# Interface.net
KiCad netlist of a schematic drawn in EAGLE
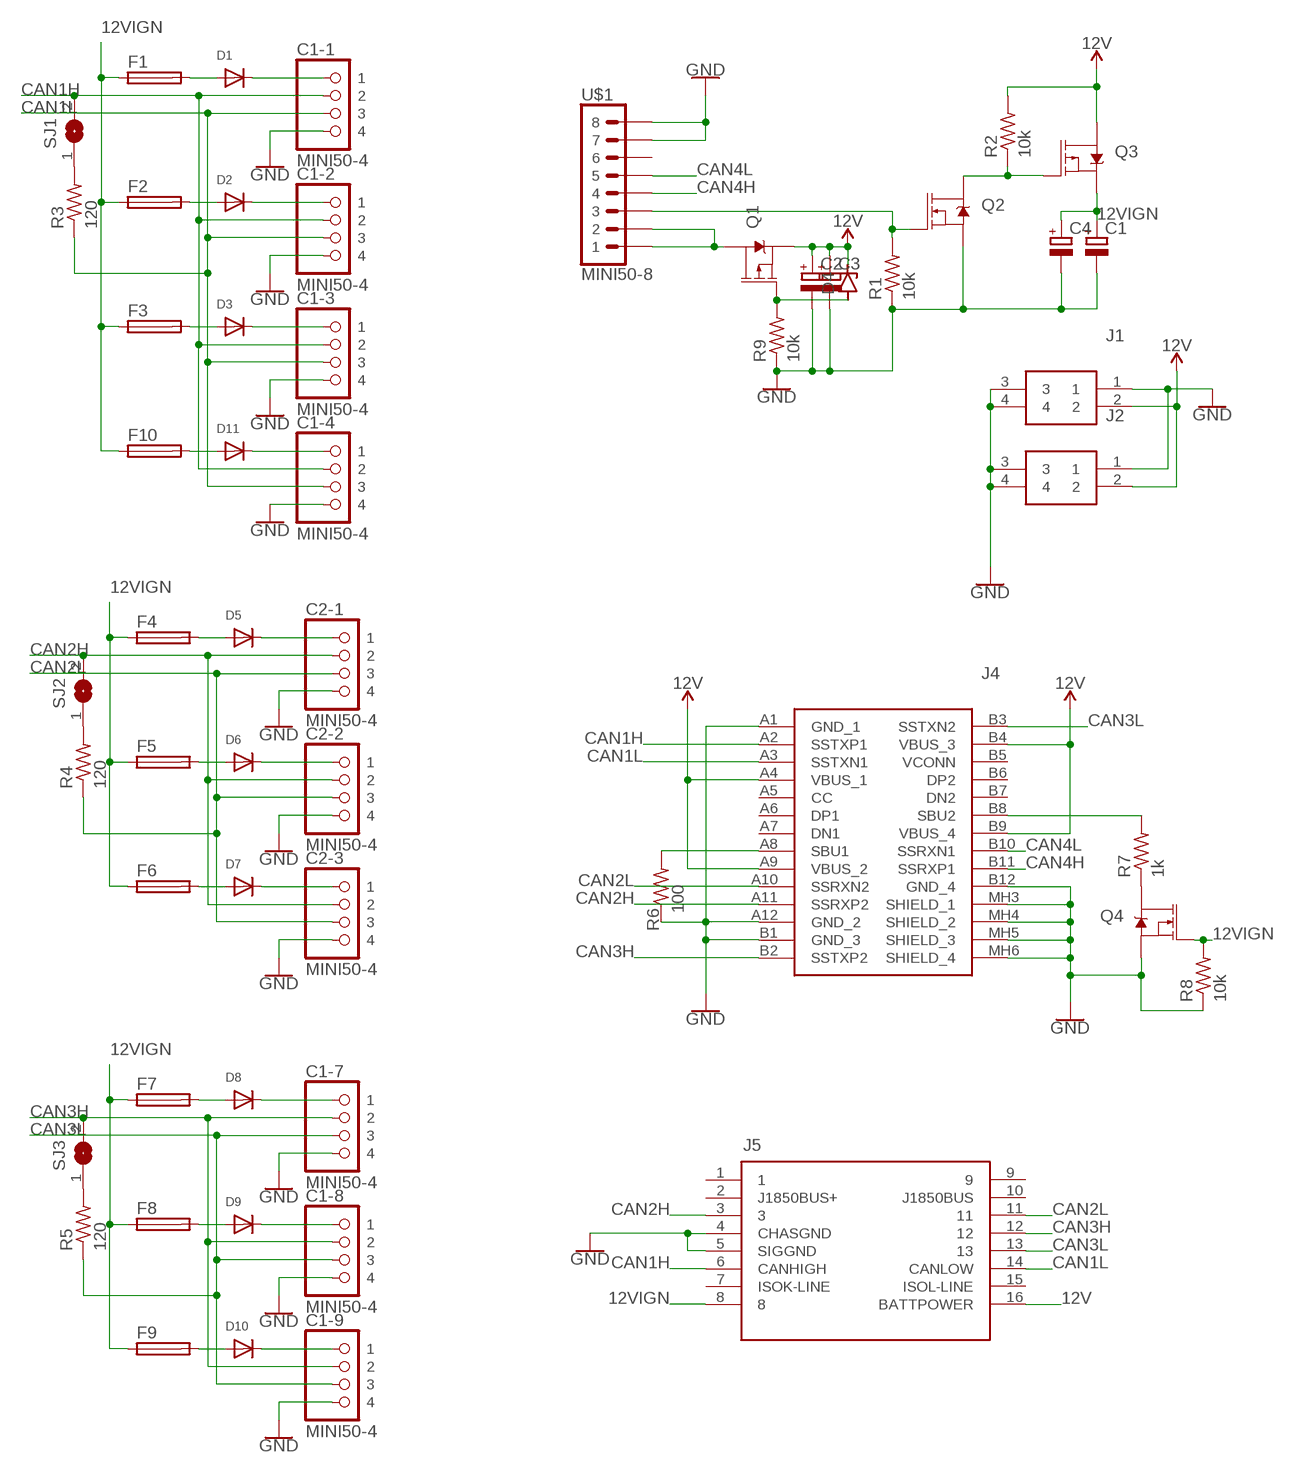
[diagram p0: schematic, sheet 1]

(export (version "E")
  (design (tool "Eeschema 10.0.6"))
  (components
    (comp (ref "C1")
      (value "CPOL-EU153CLV-1010")
      (footprint "eagle-import:153CLV-1010")
      (libsource (lib "eagle-import") (part "CPOL-EU153CLV-1010"))
    )
    (comp (ref "C1-1")
      (value "MINI50-4")
      (footprint "eagle-import:MINI50")
      (libsource (lib "eagle-import") (part "MINI50-4"))
    )
    (comp (ref "C1-2")
      (value "MINI50-4")
      (footprint "eagle-import:MINI50")
      (libsource (lib "eagle-import") (part "MINI50-4"))
    )
    (comp (ref "C1-3")
      (value "MINI50-4")
      (footprint "eagle-import:MINI50")
      (libsource (lib "eagle-import") (part "MINI50-4"))
    )
    (comp (ref "C1-4")
      (value "MINI50-4")
      (footprint "eagle-import:MINI50")
      (libsource (lib "eagle-import") (part "MINI50-4"))
    )
    (comp (ref "C1-7")
      (value "MINI50-4")
      (footprint "eagle-import:MINI50")
      (libsource (lib "eagle-import") (part "MINI50-4"))
    )
    (comp (ref "C1-8")
      (value "MINI50-4")
      (footprint "eagle-import:MINI50")
      (libsource (lib "eagle-import") (part "MINI50-4"))
    )
    (comp (ref "C1-9")
      (value "MINI50-4")
      (footprint "eagle-import:MINI50")
      (libsource (lib "eagle-import") (part "MINI50-4"))
    )
    (comp (ref "C2")
      (value "CPOL-EU153CLV-1010")
      (footprint "eagle-import:153CLV-1010")
      (libsource (lib "eagle-import") (part "CPOL-EU153CLV-1010"))
    )
    (comp (ref "C2-1")
      (value "MINI50-4")
      (footprint "eagle-import:MINI50")
      (libsource (lib "eagle-import") (part "MINI50-4"))
    )
    (comp (ref "C2-2")
      (value "MINI50-4")
      (footprint "eagle-import:MINI50")
      (libsource (lib "eagle-import") (part "MINI50-4"))
    )
    (comp (ref "C2-3")
      (value "MINI50-4")
      (footprint "eagle-import:MINI50")
      (libsource (lib "eagle-import") (part "MINI50-4"))
    )
    (comp (ref "C3")
      (value "CPOL-EU153CLV-0505")
      (footprint "eagle-import:153CLV-0505")
      (libsource (lib "eagle-import") (part "CPOL-EU153CLV-0505"))
    )
    (comp (ref "C4")
      (value "CPOL-EU153CLV-0505")
      (footprint "eagle-import:153CLV-0505")
      (libsource (lib "eagle-import") (part "CPOL-EU153CLV-0505"))
    )
    (comp (ref "D1")
      (value "DIODESOD-323F")
      (footprint "eagle-import:SOD-323F")
      (libsource (lib "eagle-import") (part "DIODESOD-323F"))
    )
    (comp (ref "D2")
      (value "DIODESOD-323F")
      (footprint "eagle-import:SOD-323F")
      (libsource (lib "eagle-import") (part "DIODESOD-323F"))
    )
    (comp (ref "D3")
      (value "DIODESOD-323F")
      (footprint "eagle-import:SOD-323F")
      (libsource (lib "eagle-import") (part "DIODESOD-323F"))
    )
    (comp (ref "D4")
      (value "ZENER_DO-219-AB(SOD123F)")
      (footprint "eagle-import:SODFL3718X115")
      (libsource (lib "eagle-import") (part "ZENERDO-219-AB(SOD123F)_"))
    )
    (comp (ref "D5")
      (value "DIODESOD-323F")
      (footprint "eagle-import:SOD-323F")
      (libsource (lib "eagle-import") (part "DIODESOD-323F"))
    )
    (comp (ref "D6")
      (value "DIODESOD-323F")
      (footprint "eagle-import:SOD-323F")
      (libsource (lib "eagle-import") (part "DIODESOD-323F"))
    )
    (comp (ref "D7")
      (value "DIODESOD-323F")
      (footprint "eagle-import:SOD-323F")
      (libsource (lib "eagle-import") (part "DIODESOD-323F"))
    )
    (comp (ref "D8")
      (value "DIODESOD-323F")
      (footprint "eagle-import:SOD-323F")
      (libsource (lib "eagle-import") (part "DIODESOD-323F"))
    )
    (comp (ref "D9")
      (value "DIODESOD-323F")
      (footprint "eagle-import:SOD-323F")
      (libsource (lib "eagle-import") (part "DIODESOD-323F"))
    )
    (comp (ref "D10")
      (value "DIODESOD-323F")
      (footprint "eagle-import:SOD-323F")
      (libsource (lib "eagle-import") (part "DIODESOD-323F"))
    )
    (comp (ref "D11")
      (value "DIODESOD-323F")
      (footprint "eagle-import:SOD-323F")
      (libsource (lib "eagle-import") (part "DIODESOD-323F"))
    )
    (comp (ref "F1")
      (value "FUSE_CHIP-1206(3216-METRIC)")
      (footprint "eagle-import:FUSC3215X82N")
      (libsource (lib "eagle-import") (part "FUSECHIP-1206(3216-METRIC)_"))
    )
    (comp (ref "F2")
      (value "FUSE_CHIP-1206(3216-METRIC)")
      (footprint "eagle-import:FUSC3215X82N")
      (libsource (lib "eagle-import") (part "FUSECHIP-1206(3216-METRIC)_"))
    )
    (comp (ref "F3")
      (value "FUSE_CHIP-1206(3216-METRIC)")
      (footprint "eagle-import:FUSC3215X82N")
      (libsource (lib "eagle-import") (part "FUSECHIP-1206(3216-METRIC)_"))
    )
    (comp (ref "F4")
      (value "FUSE_CHIP-1206(3216-METRIC)")
      (footprint "eagle-import:FUSC3215X82N")
      (libsource (lib "eagle-import") (part "FUSECHIP-1206(3216-METRIC)_"))
    )
    (comp (ref "F5")
      (value "FUSE_CHIP-1206(3216-METRIC)")
      (footprint "eagle-import:FUSC3215X82N")
      (libsource (lib "eagle-import") (part "FUSECHIP-1206(3216-METRIC)_"))
    )
    (comp (ref "F6")
      (value "FUSE_CHIP-1206(3216-METRIC)")
      (footprint "eagle-import:FUSC3215X82N")
      (libsource (lib "eagle-import") (part "FUSECHIP-1206(3216-METRIC)_"))
    )
    (comp (ref "F7")
      (value "FUSE_CHIP-1206(3216-METRIC)")
      (footprint "eagle-import:FUSC3215X82N")
      (libsource (lib "eagle-import") (part "FUSECHIP-1206(3216-METRIC)_"))
    )
    (comp (ref "F8")
      (value "FUSE_CHIP-1206(3216-METRIC)")
      (footprint "eagle-import:FUSC3215X82N")
      (libsource (lib "eagle-import") (part "FUSECHIP-1206(3216-METRIC)_"))
    )
    (comp (ref "F9")
      (value "FUSE_CHIP-1206(3216-METRIC)")
      (footprint "eagle-import:FUSC3215X82N")
      (libsource (lib "eagle-import") (part "FUSECHIP-1206(3216-METRIC)_"))
    )
    (comp (ref "F10")
      (value "FUSE_CHIP-1206(3216-METRIC)")
      (footprint "eagle-import:FUSC3215X82N")
      (libsource (lib "eagle-import") (part "FUSECHIP-1206(3216-METRIC)_"))
    )
    (comp (ref "J1")
      (value "34912-8020")
      (footprint "eagle-import:0349128020")
      (fields (field (name "MOUSER_PART_NUMBER") "538-34912-8020"))
      (libsource (lib "eagle-import") (part "34912-8020"))
    )
    (comp (ref "J2")
      (value "34912-8020")
      (footprint "eagle-import:0349128020")
      (fields (field (name "MOUSER_PART_NUMBER") "538-34912-8020"))
      (libsource (lib "eagle-import") (part "34912-8020"))
    )
    (comp (ref "J4")
      (value "632722110112")
      (footprint "eagle-import:632722110112")
      (fields (field (name "MOUSER_PART_NUMBER") "710-632722110112"))
      (libsource (lib "eagle-import") (part "632722110112"))
    )
    (comp (ref "J5")
      (value "OBDII-FEMALEFEMALE")
      (footprint "eagle-import:OBDII-FEMALE")
      (libsource (lib "eagle-import") (part "OBDII-FEMALEFEMALE"))
    )
    (comp (ref "Q1")
      (value "6.5A/20V/35mΩ")
      (footprint "eagle-import:SO08")
      (libsource (lib "eagle-import") (part "MOSFET_PCH-KI4435DY"))
    )
    (comp (ref "Q2")
      (value "5.8A/30V/35mΩ")
      (footprint "eagle-import:SOT23-3")
      (libsource (lib "eagle-import") (part "MOSFET-NCH-AO3404A"))
    )
    (comp (ref "Q3")
      (value "6.5A/20V/35mΩ")
      (footprint "eagle-import:SO08")
      (libsource (lib "eagle-import") (part "MOSFET_PCH-KI4435DY"))
    )
    (comp (ref "Q4")
      (value "5.8A/30V/35mΩ")
      (footprint "eagle-import:SOT23-3")
      (libsource (lib "eagle-import") (part "MOSFET-NCH-AO3404A"))
    )
    (comp (ref "R1")
      (value "10k")
      (footprint "eagle-import:0402-R")
      (libsource (lib "eagle-import") (part "R0402"))
    )
    (comp (ref "R2")
      (value "10k")
      (footprint "eagle-import:0402-R")
      (libsource (lib "eagle-import") (part "R0402"))
    )
    (comp (ref "R3")
      (value "120")
      (footprint "eagle-import:0402-R")
      (libsource (lib "eagle-import") (part "R0402"))
    )
    (comp (ref "R4")
      (value "120")
      (footprint "eagle-import:0402-R")
      (libsource (lib "eagle-import") (part "R0402"))
    )
    (comp (ref "R5")
      (value "120")
      (footprint "eagle-import:0402-R")
      (libsource (lib "eagle-import") (part "R0402"))
    )
    (comp (ref "R6")
      (value "100")
      (footprint "eagle-import:0402-R")
      (libsource (lib "eagle-import") (part "R0402"))
    )
    (comp (ref "R7")
      (value "1k")
      (footprint "eagle-import:0402-R")
      (libsource (lib "eagle-import") (part "R0402"))
    )
    (comp (ref "R8")
      (value "10k")
      (footprint "eagle-import:0402-R")
      (libsource (lib "eagle-import") (part "R0402"))
    )
    (comp (ref "R9")
      (value "10k")
      (footprint "eagle-import:0402-R")
      (libsource (lib "eagle-import") (part "R0402"))
    )
    (comp (ref "SJ1") (value "SJ") (footprint "eagle-import:SJ") (libsource (lib "eagle-import") (part "SJ")))
    (comp (ref "SJ2") (value "SJ") (footprint "eagle-import:SJ") (libsource (lib "eagle-import") (part "SJ")))
    (comp (ref "SJ3") (value "SJ") (footprint "eagle-import:SJ") (libsource (lib "eagle-import") (part "SJ")))
    (comp (ref "U$1")
      (value "MINI50-8")
      (footprint "eagle-import:MINI50-8")
      (libsource (lib "eagle-import") (part "MINI50-8"))
    )
  )
  (nets
    (net (code "1") (name "/12VIGN") (class "Default")
      (node (ref "C1") (pin "+") (pinfunction "+_+") (pintype "passive"))
      (node (ref "C4") (pin "+") (pinfunction "+_+") (pintype "passive"))
      (node (ref "F1") (pin "1") (pinfunction "1_1") (pintype "passive"))
      (node (ref "F10") (pin "1") (pinfunction "1_1") (pintype "passive"))
      (node (ref "F2") (pin "1") (pinfunction "1_1") (pintype "passive"))
      (node (ref "F3") (pin "1") (pinfunction "1_1") (pintype "passive"))
      (node (ref "F4") (pin "1") (pinfunction "1_1") (pintype "passive"))
      (node (ref "F5") (pin "1") (pinfunction "1_1") (pintype "passive"))
      (node (ref "F6") (pin "1") (pinfunction "1_1") (pintype "passive"))
      (node (ref "F7") (pin "1") (pinfunction "1_1") (pintype "passive"))
      (node (ref "F8") (pin "1") (pinfunction "1_1") (pintype "passive"))
      (node (ref "F9") (pin "1") (pinfunction "1_1") (pintype "passive"))
      (node (ref "J5") (pin "8") (pinfunction "8_8") (pintype "bidirectional"))
      (node (ref "Q3") (pin "1") (pinfunction "S_1") (pintype "bidirectional"))
      (node (ref "Q3") (pin "2") (pinfunction "S_2") (pintype "bidirectional"))
      (node (ref "Q3") (pin "3") (pinfunction "S_3") (pintype "bidirectional"))
      (node (ref "Q4") (pin "1") (pinfunction "G_1") (pintype "bidirectional"))
      (node (ref "R8") (pin "2") (pinfunction "2_2") (pintype "passive"))
    )
    (net (code "2") (name "/CAN1H") (class "Default")
      (node (ref "C1-1") (pin "3") (pinfunction "2_3") (pintype "passive"))
      (node (ref "C1-2") (pin "3") (pinfunction "2_3") (pintype "passive"))
      (node (ref "C1-3") (pin "3") (pinfunction "2_3") (pintype "passive"))
      (node (ref "C1-4") (pin "3") (pinfunction "2_3") (pintype "passive"))
      (node (ref "J4") (pin "A2") (pinfunction "SSTXP1_A2") (pintype "bidirectional"))
      (node (ref "J5") (pin "6") (pinfunction "CANHIGH_6") (pintype "bidirectional"))
      (node (ref "SJ1") (pin "2") (pinfunction "2_2") (pintype "passive"))
    )
    (net (code "3") (name "/CAN1L") (class "Default")
      (node (ref "C1-1") (pin "2") (pinfunction "3_2") (pintype "passive"))
      (node (ref "C1-2") (pin "2") (pinfunction "3_2") (pintype "passive"))
      (node (ref "C1-3") (pin "2") (pinfunction "3_2") (pintype "passive"))
      (node (ref "C1-4") (pin "2") (pinfunction "3_2") (pintype "passive"))
      (node (ref "J4") (pin "A3") (pinfunction "SSTXN1_A3") (pintype "bidirectional"))
      (node (ref "J5") (pin "14") (pinfunction "CANLOW_14") (pintype "bidirectional"))
      (node (ref "R3") (pin "1") (pinfunction "1_1") (pintype "passive"))
    )
    (net (code "4") (name "/CAN2H") (class "Default")
      (node (ref "C2-1") (pin "3") (pinfunction "2_3") (pintype "passive"))
      (node (ref "C2-2") (pin "3") (pinfunction "2_3") (pintype "passive"))
      (node (ref "C2-3") (pin "3") (pinfunction "2_3") (pintype "passive"))
      (node (ref "J4") (pin "A11") (pinfunction "SSRXP2_A11") (pintype "bidirectional"))
      (node (ref "J5") (pin "3") (pinfunction "3_3") (pintype "bidirectional"))
      (node (ref "SJ2") (pin "2") (pinfunction "2_2") (pintype "passive"))
    )
    (net (code "5") (name "/CAN2L") (class "Default")
      (node (ref "C2-1") (pin "2") (pinfunction "3_2") (pintype "passive"))
      (node (ref "C2-2") (pin "2") (pinfunction "3_2") (pintype "passive"))
      (node (ref "C2-3") (pin "2") (pinfunction "3_2") (pintype "passive"))
      (node (ref "J4") (pin "A10") (pinfunction "SSRXN2_A10") (pintype "bidirectional"))
      (node (ref "J5") (pin "11") (pinfunction "11_11") (pintype "bidirectional"))
      (node (ref "R4") (pin "1") (pinfunction "1_1") (pintype "passive"))
    )
    (net (code "6") (name "/CAN3H") (class "Default")
      (node (ref "C1-7") (pin "3") (pinfunction "2_3") (pintype "passive"))
      (node (ref "C1-8") (pin "3") (pinfunction "2_3") (pintype "passive"))
      (node (ref "C1-9") (pin "3") (pinfunction "2_3") (pintype "passive"))
      (node (ref "J4") (pin "B2") (pinfunction "SSTXP2_B2") (pintype "bidirectional"))
      (node (ref "J5") (pin "12") (pinfunction "12_12") (pintype "bidirectional"))
      (node (ref "SJ3") (pin "2") (pinfunction "2_2") (pintype "passive"))
    )
    (net (code "7") (name "/CAN3L") (class "Default")
      (node (ref "C1-7") (pin "2") (pinfunction "3_2") (pintype "passive"))
      (node (ref "C1-8") (pin "2") (pinfunction "3_2") (pintype "passive"))
      (node (ref "C1-9") (pin "2") (pinfunction "3_2") (pintype "passive"))
      (node (ref "J4") (pin "B3") (pinfunction "SSTXN2_B3") (pintype "bidirectional"))
      (node (ref "J5") (pin "13") (pinfunction "13_13") (pintype "bidirectional"))
      (node (ref "R5") (pin "1") (pinfunction "1_1") (pintype "passive"))
    )
    (net (code "8") (name "/CAN4H") (class "Default")
      (node (ref "J4") (pin "B11") (pinfunction "SSRXP1_B11") (pintype "bidirectional"))
      (node (ref "U$1") (pin "P$4") (pinfunction "4_P$4") (pintype "passive"))
    )
    (net (code "9") (name "/CAN4L") (class "Default")
      (node (ref "J4") (pin "B10") (pinfunction "SSRXN1_B10") (pintype "bidirectional"))
      (node (ref "U$1") (pin "P$5") (pinfunction "5_P$5") (pintype "passive"))
    )
    (net (code "10") (name "12V") (class "Default")
      (node (ref "C2") (pin "+") (pinfunction "+_+") (pintype "passive"))
      (node (ref "C3") (pin "+") (pinfunction "+_+") (pintype "passive"))
      (node (ref "D4") (pin "2") (pinfunction "C_2") (pintype "passive"))
      (node (ref "J1") (pin "2") (pinfunction "2_2") (pintype "bidirectional"))
      (node (ref "J2") (pin "2") (pinfunction "2_2") (pintype "bidirectional"))
      (node (ref "J4") (pin "A4") (pinfunction "VBUS_1_A4") (pintype "bidirectional"))
      (node (ref "J4") (pin "A9") (pinfunction "VBUS_2_A9") (pintype "bidirectional"))
      (node (ref "J4") (pin "B4") (pinfunction "VBUS_3_B4") (pintype "bidirectional"))
      (node (ref "J4") (pin "B9") (pinfunction "VBUS_4_B9") (pintype "bidirectional"))
      (node (ref "J5") (pin "16") (pinfunction "BATTPOWER_16") (pintype "bidirectional"))
      (node (ref "Q1") (pin "1") (pinfunction "S_1") (pintype "bidirectional"))
      (node (ref "Q1") (pin "2") (pinfunction "S_2") (pintype "bidirectional"))
      (node (ref "Q1") (pin "3") (pinfunction "S_3") (pintype "bidirectional"))
      (node (ref "Q3") (pin "5") (pinfunction "D_5") (pintype "bidirectional"))
      (node (ref "Q3") (pin "6") (pinfunction "D_6") (pintype "bidirectional"))
      (node (ref "Q3") (pin "7") (pinfunction "D_7") (pintype "bidirectional"))
      (node (ref "Q3") (pin "8") (pinfunction "D_8") (pintype "bidirectional"))
      (node (ref "R2") (pin "2") (pinfunction "2_2") (pintype "passive"))
    )
    (net (code "11") (name "GND") (class "Default")
      (node (ref "C1") (pin "-") (pinfunction "-_-") (pintype "passive"))
      (node (ref "C1-1") (pin "1") (pinfunction "4_1") (pintype "passive"))
      (node (ref "C1-2") (pin "1") (pinfunction "4_1") (pintype "passive"))
      (node (ref "C1-3") (pin "1") (pinfunction "4_1") (pintype "passive"))
      (node (ref "C1-4") (pin "1") (pinfunction "4_1") (pintype "passive"))
      (node (ref "C1-7") (pin "1") (pinfunction "4_1") (pintype "passive"))
      (node (ref "C1-8") (pin "1") (pinfunction "4_1") (pintype "passive"))
      (node (ref "C1-9") (pin "1") (pinfunction "4_1") (pintype "passive"))
      (node (ref "C2") (pin "-") (pinfunction "-_-") (pintype "passive"))
      (node (ref "C2-1") (pin "1") (pinfunction "4_1") (pintype "passive"))
      (node (ref "C2-2") (pin "1") (pinfunction "4_1") (pintype "passive"))
      (node (ref "C2-3") (pin "1") (pinfunction "4_1") (pintype "passive"))
      (node (ref "C3") (pin "-") (pinfunction "-_-") (pintype "passive"))
      (node (ref "C4") (pin "-") (pinfunction "-_-") (pintype "passive"))
      (node (ref "J1") (pin "1") (pinfunction "1_1") (pintype "bidirectional"))
      (node (ref "J1") (pin "3") (pinfunction "3_3") (pintype "bidirectional"))
      (node (ref "J1") (pin "4") (pinfunction "4_4") (pintype "bidirectional"))
      (node (ref "J2") (pin "1") (pinfunction "1_1") (pintype "bidirectional"))
      (node (ref "J2") (pin "3") (pinfunction "3_3") (pintype "bidirectional"))
      (node (ref "J2") (pin "4") (pinfunction "4_4") (pintype "bidirectional"))
      (node (ref "J4") (pin "A1") (pinfunction "GND_1_A1") (pintype "bidirectional"))
      (node (ref "J4") (pin "A12") (pinfunction "GND_2_A12") (pintype "bidirectional"))
      (node (ref "J4") (pin "B1") (pinfunction "GND_3_B1") (pintype "bidirectional"))
      (node (ref "J4") (pin "B12") (pinfunction "GND_4_B12") (pintype "bidirectional"))
      (node (ref "J4") (pin "MH3") (pinfunction "SHIELD_1_MH3") (pintype "bidirectional"))
      (node (ref "J4") (pin "MH4") (pinfunction "SHIELD_2_MH4") (pintype "bidirectional"))
      (node (ref "J4") (pin "MH5") (pinfunction "SHIELD_3_MH5") (pintype "bidirectional"))
      (node (ref "J4") (pin "MH6") (pinfunction "SHIELD_4_MH6") (pintype "bidirectional"))
      (node (ref "J5") (pin "4") (pinfunction "CHASGND_4") (pintype "bidirectional"))
      (node (ref "J5") (pin "5") (pinfunction "SIGGND_5") (pintype "bidirectional"))
      (node (ref "Q2") (pin "2") (pinfunction "S_2") (pintype "bidirectional"))
      (node (ref "Q4") (pin "2") (pinfunction "S_2") (pintype "bidirectional"))
      (node (ref "R1") (pin "1") (pinfunction "1_1") (pintype "passive"))
      (node (ref "R6") (pin "1") (pinfunction "1_1") (pintype "passive"))
      (node (ref "R8") (pin "1") (pinfunction "1_1") (pintype "passive"))
      (node (ref "R9") (pin "1") (pinfunction "1_1") (pintype "passive"))
      (node (ref "U$1") (pin "P$7") (pinfunction "7_P$7") (pintype "passive"))
      (node (ref "U$1") (pin "P$8") (pinfunction "8_P$8") (pintype "passive"))
    )
    (net (code "12") (name "Net-(C1-1-1)") (class "Default")
      (node (ref "C1-1") (pin "4") (pinfunction "1_4") (pintype "passive"))
      (node (ref "D1") (pin "C") (pinfunction "C_C") (pintype "passive"))
    )
    (net (code "13") (name "Net-(C1-2-1)") (class "Default")
      (node (ref "C1-2") (pin "4") (pinfunction "1_4") (pintype "passive"))
      (node (ref "D2") (pin "C") (pinfunction "C_C") (pintype "passive"))
    )
    (net (code "14") (name "Net-(C1-3-1)") (class "Default")
      (node (ref "C1-3") (pin "4") (pinfunction "1_4") (pintype "passive"))
      (node (ref "D3") (pin "C") (pinfunction "C_C") (pintype "passive"))
    )
    (net (code "15") (name "Net-(C1-4-1)") (class "Default")
      (node (ref "C1-4") (pin "4") (pinfunction "1_4") (pintype "passive"))
      (node (ref "D11") (pin "C") (pinfunction "C_C") (pintype "passive"))
    )
    (net (code "16") (name "Net-(C1-7-1)") (class "Default")
      (node (ref "C1-7") (pin "4") (pinfunction "1_4") (pintype "passive"))
      (node (ref "D8") (pin "C") (pinfunction "C_C") (pintype "passive"))
    )
    (net (code "17") (name "Net-(C1-8-1)") (class "Default")
      (node (ref "C1-8") (pin "4") (pinfunction "1_4") (pintype "passive"))
      (node (ref "D9") (pin "C") (pinfunction "C_C") (pintype "passive"))
    )
    (net (code "18") (name "Net-(C1-9-1)") (class "Default")
      (node (ref "C1-9") (pin "4") (pinfunction "1_4") (pintype "passive"))
      (node (ref "D10") (pin "C") (pinfunction "C_C") (pintype "passive"))
    )
    (net (code "19") (name "Net-(C2-1-1)") (class "Default")
      (node (ref "C2-1") (pin "4") (pinfunction "1_4") (pintype "passive"))
      (node (ref "D5") (pin "C") (pinfunction "C_C") (pintype "passive"))
    )
    (net (code "20") (name "Net-(C2-2-1)") (class "Default")
      (node (ref "C2-2") (pin "4") (pinfunction "1_4") (pintype "passive"))
      (node (ref "D6") (pin "C") (pinfunction "C_C") (pintype "passive"))
    )
    (net (code "21") (name "Net-(C2-3-1)") (class "Default")
      (node (ref "C2-3") (pin "4") (pinfunction "1_4") (pintype "passive"))
      (node (ref "D7") (pin "C") (pinfunction "C_C") (pintype "passive"))
    )
    (net (code "22") (name "Net-(D1-PadA)") (class "Default")
      (node (ref "D1") (pin "A") (pinfunction "A_A") (pintype "passive"))
      (node (ref "F1") (pin "2") (pinfunction "2_2") (pintype "passive"))
    )
    (net (code "23") (name "Net-(D2-PadA)") (class "Default")
      (node (ref "D2") (pin "A") (pinfunction "A_A") (pintype "passive"))
      (node (ref "F2") (pin "2") (pinfunction "2_2") (pintype "passive"))
    )
    (net (code "24") (name "Net-(D3-PadA)") (class "Default")
      (node (ref "D3") (pin "A") (pinfunction "A_A") (pintype "passive"))
      (node (ref "F3") (pin "2") (pinfunction "2_2") (pintype "passive"))
    )
    (net (code "25") (name "Net-(D4-A)") (class "Default")
      (node (ref "D4") (pin "1") (pinfunction "A_1") (pintype "passive"))
      (node (ref "Q1") (pin "4") (pinfunction "G_4") (pintype "bidirectional"))
      (node (ref "R9") (pin "2") (pinfunction "2_2") (pintype "passive"))
    )
    (net (code "26") (name "Net-(D5-PadA)") (class "Default")
      (node (ref "D5") (pin "A") (pinfunction "A_A") (pintype "passive"))
      (node (ref "F4") (pin "2") (pinfunction "2_2") (pintype "passive"))
    )
    (net (code "27") (name "Net-(D6-PadA)") (class "Default")
      (node (ref "D6") (pin "A") (pinfunction "A_A") (pintype "passive"))
      (node (ref "F5") (pin "2") (pinfunction "2_2") (pintype "passive"))
    )
    (net (code "28") (name "Net-(D7-PadA)") (class "Default")
      (node (ref "D7") (pin "A") (pinfunction "A_A") (pintype "passive"))
      (node (ref "F6") (pin "2") (pinfunction "2_2") (pintype "passive"))
    )
    (net (code "29") (name "Net-(D8-PadA)") (class "Default")
      (node (ref "D8") (pin "A") (pinfunction "A_A") (pintype "passive"))
      (node (ref "F7") (pin "2") (pinfunction "2_2") (pintype "passive"))
    )
    (net (code "30") (name "Net-(D9-PadA)") (class "Default")
      (node (ref "D9") (pin "A") (pinfunction "A_A") (pintype "passive"))
      (node (ref "F8") (pin "2") (pinfunction "2_2") (pintype "passive"))
    )
    (net (code "31") (name "Net-(D10-PadA)") (class "Default")
      (node (ref "D10") (pin "A") (pinfunction "A_A") (pintype "passive"))
      (node (ref "F9") (pin "2") (pinfunction "2_2") (pintype "passive"))
    )
    (net (code "32") (name "Net-(D11-PadA)") (class "Default")
      (node (ref "D11") (pin "A") (pinfunction "A_A") (pintype "passive"))
      (node (ref "F10") (pin "2") (pinfunction "2_2") (pintype "passive"))
    )
    (net (code "33") (name "Net-(J4-SBU1)") (class "Default")
      (node (ref "J4") (pin "A8") (pinfunction "SBU1_A8") (pintype "bidirectional"))
      (node (ref "R6") (pin "2") (pinfunction "2_2") (pintype "passive"))
    )
    (net (code "34") (name "Net-(J4-SBU2)") (class "Default")
      (node (ref "J4") (pin "B8") (pinfunction "SBU2_B8") (pintype "bidirectional"))
      (node (ref "R7") (pin "2") (pinfunction "2_2") (pintype "passive"))
    )
    (net (code "35") (name "Net-(Q2-D)") (class "Default")
      (node (ref "Q2") (pin "3") (pinfunction "D_3") (pintype "bidirectional"))
      (node (ref "Q3") (pin "4") (pinfunction "G_4") (pintype "bidirectional"))
      (node (ref "R2") (pin "1") (pinfunction "1_1") (pintype "passive"))
    )
    (net (code "36") (name "Net-(Q2-G)") (class "Default")
      (node (ref "Q2") (pin "1") (pinfunction "G_1") (pintype "bidirectional"))
      (node (ref "R1") (pin "2") (pinfunction "2_2") (pintype "passive"))
      (node (ref "U$1") (pin "P$3") (pinfunction "3_P$3") (pintype "passive"))
    )
    (net (code "37") (name "Net-(Q4-D)") (class "Default")
      (node (ref "Q4") (pin "3") (pinfunction "D_3") (pintype "bidirectional"))
      (node (ref "R7") (pin "1") (pinfunction "1_1") (pintype "passive"))
    )
    (net (code "38") (name "Net-(R3-Pad2)") (class "Default")
      (node (ref "R3") (pin "2") (pinfunction "2_2") (pintype "passive"))
      (node (ref "SJ1") (pin "1") (pinfunction "1_1") (pintype "passive"))
    )
    (net (code "39") (name "Net-(R4-Pad2)") (class "Default")
      (node (ref "R4") (pin "2") (pinfunction "2_2") (pintype "passive"))
      (node (ref "SJ2") (pin "1") (pinfunction "1_1") (pintype "passive"))
    )
    (net (code "40") (name "Net-(R5-Pad2)") (class "Default")
      (node (ref "R5") (pin "2") (pinfunction "2_2") (pintype "passive"))
      (node (ref "SJ3") (pin "1") (pinfunction "1_1") (pintype "passive"))
    )
    (net (code "41") (name "Net-(U$1-1)") (class "Default")
      (node (ref "Q1") (pin "5") (pinfunction "D_5") (pintype "bidirectional"))
      (node (ref "Q1") (pin "6") (pinfunction "D_6") (pintype "bidirectional"))
      (node (ref "Q1") (pin "7") (pinfunction "D_7") (pintype "bidirectional"))
      (node (ref "Q1") (pin "8") (pinfunction "D_8") (pintype "bidirectional"))
      (node (ref "U$1") (pin "P$1") (pinfunction "1_P$1") (pintype "passive"))
      (node (ref "U$1") (pin "P$2") (pinfunction "2_P$2") (pintype "passive"))
    )
    (net (code "42") (name "unconnected-(J4-CC-PadA5)") (class "Default")
      (node (ref "J4") (pin "A5") (pinfunction "CC_A5") (pintype "bidirectional"))
    )
    (net (code "43") (name "unconnected-(J4-DN1-PadA7)") (class "Default")
      (node (ref "J4") (pin "A7") (pinfunction "DN1_A7") (pintype "bidirectional"))
    )
    (net (code "44") (name "unconnected-(J4-DN2-PadB7)") (class "Default")
      (node (ref "J4") (pin "B7") (pinfunction "DN2_B7") (pintype "bidirectional"))
    )
    (net (code "45") (name "unconnected-(J4-DP1-PadA6)") (class "Default")
      (node (ref "J4") (pin "A6") (pinfunction "DP1_A6") (pintype "bidirectional"))
    )
    (net (code "46") (name "unconnected-(J4-DP2-PadB6)") (class "Default")
      (node (ref "J4") (pin "B6") (pinfunction "DP2_B6") (pintype "bidirectional"))
    )
    (net (code "47") (name "unconnected-(J4-VCONN-PadB5)") (class "Default")
      (node (ref "J4") (pin "B5") (pinfunction "VCONN_B5") (pintype "bidirectional"))
    )
    (net (code "48") (name "unconnected-(J5-ISOK-LINE-Pad7)") (class "Default")
      (node (ref "J5") (pin "7") (pinfunction "ISOK-LINE_7") (pintype "bidirectional"))
    )
    (net (code "49") (name "unconnected-(J5-ISOL-LINE-Pad15)") (class "Default")
      (node (ref "J5") (pin "15") (pinfunction "ISOL-LINE_15") (pintype "bidirectional"))
    )
    (net (code "50") (name "unconnected-(J5-J1850BUS+-Pad2)") (class "Default")
      (node (ref "J5") (pin "2") (pinfunction "J1850BUS+_2") (pintype "bidirectional"))
    )
    (net (code "51") (name "unconnected-(J5-J1850BUS-Pad10)") (class "Default")
      (node (ref "J5") (pin "10") (pinfunction "J1850BUS_10") (pintype "bidirectional"))
    )
    (net (code "52") (name "unconnected-(J5-Pad1)") (class "Default")
      (node (ref "J5") (pin "1") (pinfunction "1_1") (pintype "bidirectional"))
    )
    (net (code "53") (name "unconnected-(J5-Pad9)") (class "Default")
      (node (ref "J5") (pin "9") (pinfunction "9_9") (pintype "bidirectional"))
    )
    (net (code "54") (name "unconnected-(U$1-6-PadP$6)") (class "Default")
      (node (ref "U$1") (pin "P$6") (pinfunction "6_P$6") (pintype "passive"))
    )
  )
)
